# pcb_1.net
KiCad netlist of a schematic drawn in EAGLE
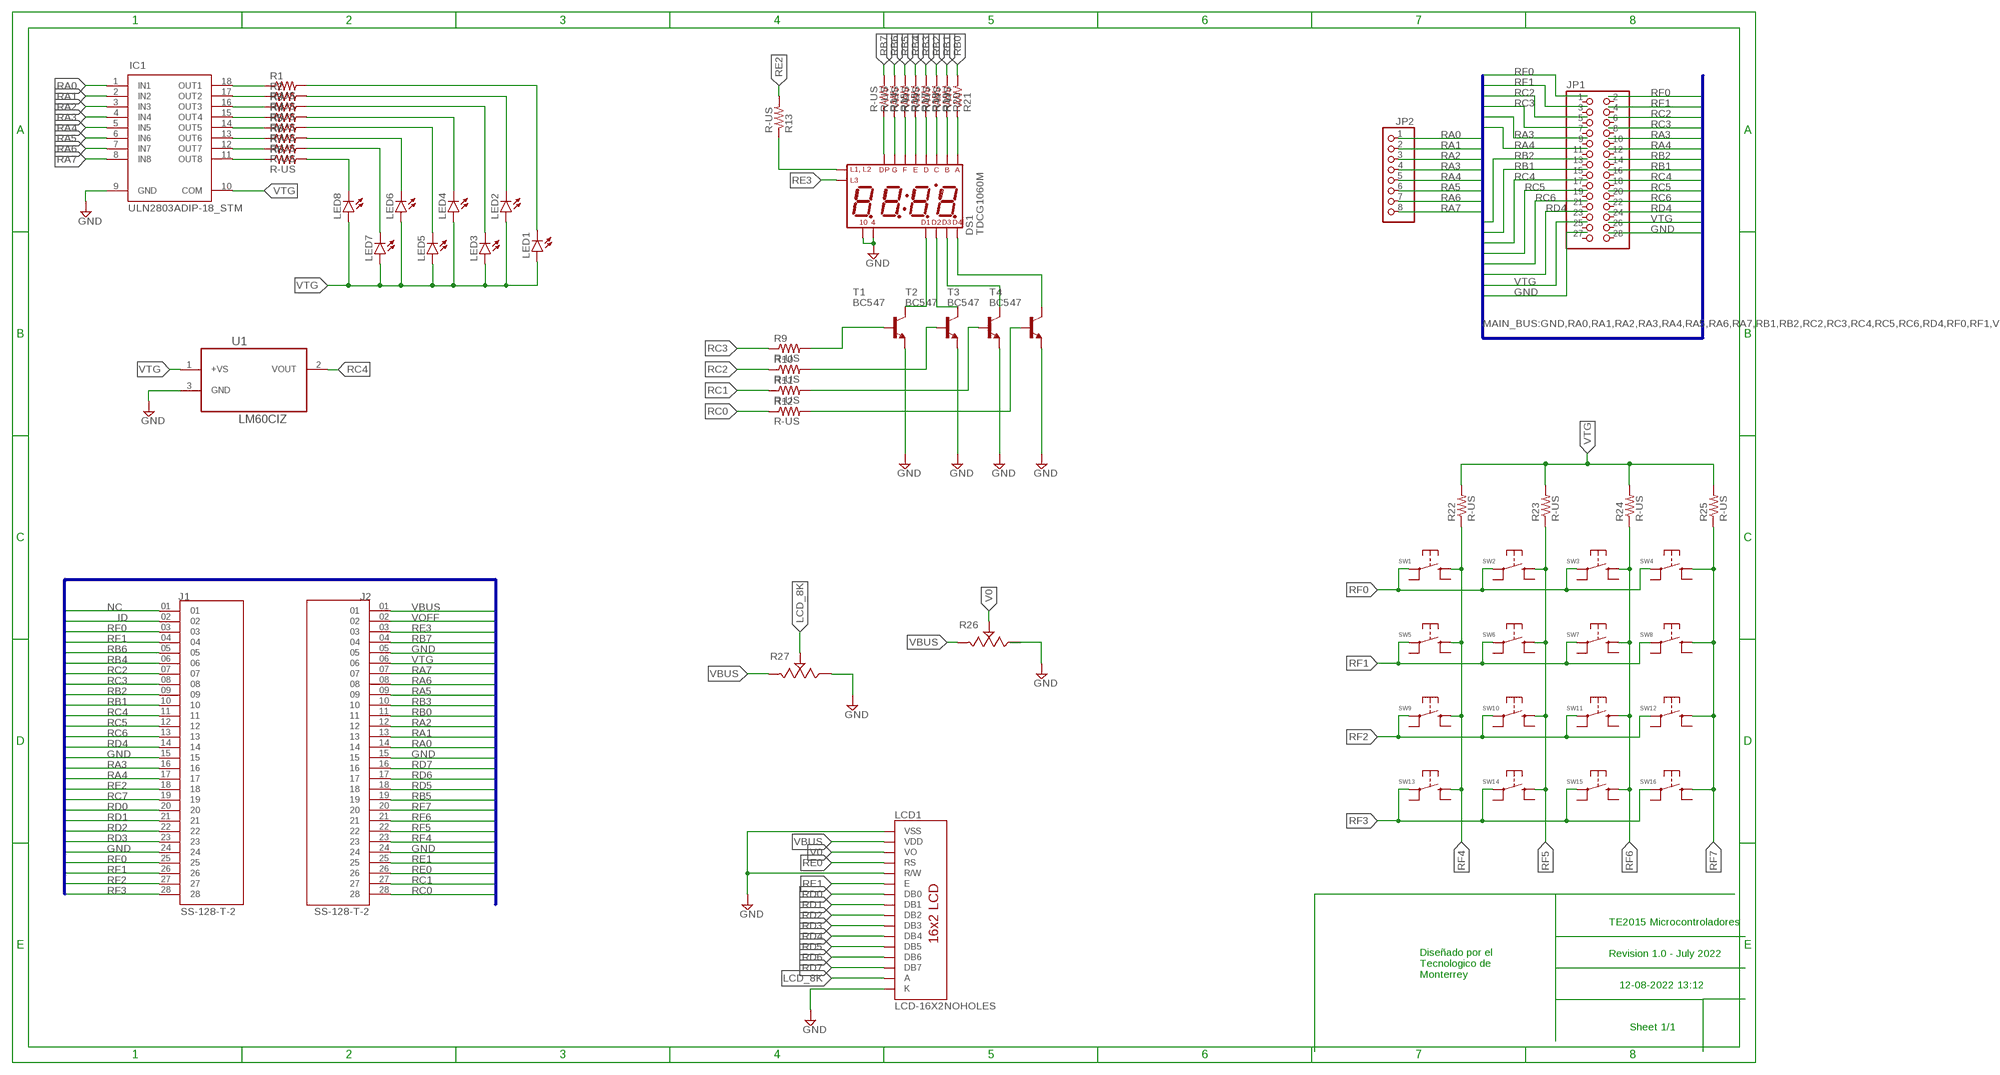
[diagram p0: schematic, sheet 1]

(export (version "E")
  (design (tool "Eeschema 10.0.6"))
  (components
    (comp (ref "DS1")
      (value "TDCG1060M")
      (footprint "eagle-import:DISPLAY_TDCG1060M")
      (fields (field (name "DIGI-KEY_PART_NUMBER") "TDCG1060M-ND") (field (name "MF") "Vishay"))
      (libsource (lib "eagle-import") (part "TDCG1060M"))
    )
    (comp (ref "IC1")
      (value "ULN2803ADIP-18_STM")
      (footprint "eagle-import:DIP-18_STM")
      (fields
        (field (name "MANUFACTURER_PART_NUMBER") "ULN2803A")
        (field (name "COPYRIGHT") "Copyright (C) 2022 Ultra Librarian. All rights reserved.")
      )
      (libsource (lib "eagle-import") (part "ULN2803ADIP-18_STM"))
    )
    (comp (ref "J1")
      (value "SS-128-T-2")
      (footprint "eagle-import:SAMTEC_SS-128-T-2")
      (fields (field (name "DIGI-KEY_PART_NUMBER") "SAM1117-28-ND") (field (name "MF") "Samtec"))
      (libsource (lib "eagle-import") (part "SS-128-T-2"))
    )
    (comp (ref "J2")
      (value "SS-128-T-2")
      (footprint "eagle-import:SAMTEC_SS-128-T-2")
      (fields (field (name "DIGI-KEY_PART_NUMBER") "SAM1117-28-ND") (field (name "MF") "Samtec"))
      (libsource (lib "eagle-import") (part "SS-128-T-2"))
    )
    (comp (ref "JP1")
      (value "PINHD-2X14-CB")
      (footprint "eagle-import:2X14-BIG")
      (libsource (lib "eagle-import") (part "PINHD-2X14-CB"))
    )
    (comp (ref "JP2")
      (value "PINHD-1X8BIG")
      (footprint "eagle-import:1X08-BIG")
      (libsource (lib "eagle-import") (part "PINHD-1X8BIG"))
    )
    (comp (ref "LCD1")
      (value "LCD-16X2NOHOLES")
      (footprint "eagle-import:LCD-16X2_NOHOLESNOSILK")
      (libsource (lib "eagle-import") (part "LCD-16X2NOHOLES"))
    )
    (comp (ref "LED1")
      (value "LED3MM")
      (footprint "eagle-import:LED3MM")
      (libsource (lib "eagle-import") (part "LED3MM"))
    )
    (comp (ref "LED2")
      (value "LED3MM")
      (footprint "eagle-import:LED3MM")
      (libsource (lib "eagle-import") (part "LED3MM"))
    )
    (comp (ref "LED3")
      (value "LED3MM")
      (footprint "eagle-import:LED3MM")
      (libsource (lib "eagle-import") (part "LED3MM"))
    )
    (comp (ref "LED4")
      (value "LED3MM")
      (footprint "eagle-import:LED3MM")
      (libsource (lib "eagle-import") (part "LED3MM"))
    )
    (comp (ref "LED5")
      (value "LED3MM")
      (footprint "eagle-import:LED3MM")
      (libsource (lib "eagle-import") (part "LED3MM"))
    )
    (comp (ref "LED6")
      (value "LED3MM")
      (footprint "eagle-import:LED3MM")
      (libsource (lib "eagle-import") (part "LED3MM"))
    )
    (comp (ref "LED7")
      (value "LED3MM")
      (footprint "eagle-import:LED3MM")
      (libsource (lib "eagle-import") (part "LED3MM"))
    )
    (comp (ref "LED8")
      (value "LED3MM")
      (footprint "eagle-import:LED3MM")
      (libsource (lib "eagle-import") (part "LED3MM"))
    )
    (comp (ref "R1")
      (value "R-US")
      (footprint "eagle-import:0207_10")
      (libsource (lib "eagle-import") (part "R-US"))
    )
    (comp (ref "R2")
      (value "R-US")
      (footprint "eagle-import:0207_10")
      (libsource (lib "eagle-import") (part "R-US"))
    )
    (comp (ref "R3")
      (value "R-US")
      (footprint "eagle-import:0207_10")
      (libsource (lib "eagle-import") (part "R-US"))
    )
    (comp (ref "R4")
      (value "R-US")
      (footprint "eagle-import:0207_10")
      (libsource (lib "eagle-import") (part "R-US"))
    )
    (comp (ref "R5")
      (value "R-US")
      (footprint "eagle-import:0207_10")
      (libsource (lib "eagle-import") (part "R-US"))
    )
    (comp (ref "R6")
      (value "R-US")
      (footprint "eagle-import:0207_10")
      (libsource (lib "eagle-import") (part "R-US"))
    )
    (comp (ref "R7")
      (value "R-US")
      (footprint "eagle-import:0207_10")
      (libsource (lib "eagle-import") (part "R-US"))
    )
    (comp (ref "R8")
      (value "R-US")
      (footprint "eagle-import:0207_10")
      (libsource (lib "eagle-import") (part "R-US"))
    )
    (comp (ref "R9")
      (value "R-US")
      (footprint "eagle-import:0207_10")
      (libsource (lib "eagle-import") (part "R-US"))
    )
    (comp (ref "R10")
      (value "R-US")
      (footprint "eagle-import:0207_10")
      (libsource (lib "eagle-import") (part "R-US"))
    )
    (comp (ref "R11")
      (value "R-US")
      (footprint "eagle-import:0207_10")
      (libsource (lib "eagle-import") (part "R-US"))
    )
    (comp (ref "R12")
      (value "R-US")
      (footprint "eagle-import:0207_10")
      (libsource (lib "eagle-import") (part "R-US"))
    )
    (comp (ref "R13")
      (value "R-US")
      (footprint "eagle-import:0207_10")
      (libsource (lib "eagle-import") (part "R-US"))
    )
    (comp (ref "R14")
      (value "R-US")
      (footprint "eagle-import:0207_10")
      (libsource (lib "eagle-import") (part "R-US"))
    )
    (comp (ref "R15")
      (value "R-US")
      (footprint "eagle-import:0207_10")
      (libsource (lib "eagle-import") (part "R-US"))
    )
    (comp (ref "R16")
      (value "R-US")
      (footprint "eagle-import:0207_10")
      (libsource (lib "eagle-import") (part "R-US"))
    )
    (comp (ref "R17")
      (value "R-US")
      (footprint "eagle-import:0207_10")
      (libsource (lib "eagle-import") (part "R-US"))
    )
    (comp (ref "R18")
      (value "R-US")
      (footprint "eagle-import:0207_10")
      (libsource (lib "eagle-import") (part "R-US"))
    )
    (comp (ref "R19")
      (value "R-US")
      (footprint "eagle-import:0207_10")
      (libsource (lib "eagle-import") (part "R-US"))
    )
    (comp (ref "R20")
      (value "R-US")
      (footprint "eagle-import:0207_10")
      (libsource (lib "eagle-import") (part "R-US"))
    )
    (comp (ref "R21")
      (value "R-US")
      (footprint "eagle-import:0207_10")
      (libsource (lib "eagle-import") (part "R-US"))
    )
    (comp (ref "R22")
      (value "R-US")
      (footprint "eagle-import:0207_10")
      (libsource (lib "eagle-import") (part "R-US"))
    )
    (comp (ref "R23")
      (value "R-US")
      (footprint "eagle-import:0207_10")
      (libsource (lib "eagle-import") (part "R-US"))
    )
    (comp (ref "R24")
      (value "R-US")
      (footprint "eagle-import:0207_10")
      (libsource (lib "eagle-import") (part "R-US"))
    )
    (comp (ref "R25")
      (value "R-US")
      (footprint "eagle-import:0207_10")
      (libsource (lib "eagle-import") (part "R-US"))
    )
    (comp (ref "R26")
      (value "3362P-1-103LF")
      (footprint "eagle-import:3362P-1-103LF")
      (fields (field (name "MANUFACTURER") "Bourns Inc.") (field (name "CREATED_PN") "PCBLayout.com"))
      (libsource (lib "eagle-import") (part "3362P-1-103LF"))
    )
    (comp (ref "R27")
      (value "3362P-1-103LF")
      (footprint "eagle-import:3362P-1-103LF")
      (fields (field (name "MANUFACTURER") "Bourns Inc.") (field (name "CREATED_PN") "PCBLayout.com"))
      (libsource (lib "eagle-import") (part "3362P-1-103LF"))
    )
    (comp (ref "SW1")
      (value "1825910-2")
      (footprint "eagle-import:TE_1825910-2")
      (fields (field (name "MF") "TE Connectivity"))
      (libsource (lib "eagle-import") (part "1825910-2"))
    )
    (comp (ref "SW2")
      (value "1825910-2")
      (footprint "eagle-import:TE_1825910-2")
      (fields (field (name "MF") "TE Connectivity"))
      (libsource (lib "eagle-import") (part "1825910-2"))
    )
    (comp (ref "SW3")
      (value "1825910-2")
      (footprint "eagle-import:TE_1825910-2")
      (fields (field (name "MF") "TE Connectivity"))
      (libsource (lib "eagle-import") (part "1825910-2"))
    )
    (comp (ref "SW4")
      (value "1825910-2")
      (footprint "eagle-import:TE_1825910-2")
      (fields (field (name "MF") "TE Connectivity"))
      (libsource (lib "eagle-import") (part "1825910-2"))
    )
    (comp (ref "SW5")
      (value "1825910-2")
      (footprint "eagle-import:TE_1825910-2")
      (fields (field (name "MF") "TE Connectivity"))
      (libsource (lib "eagle-import") (part "1825910-2"))
    )
    (comp (ref "SW6")
      (value "1825910-2")
      (footprint "eagle-import:TE_1825910-2")
      (fields (field (name "MF") "TE Connectivity"))
      (libsource (lib "eagle-import") (part "1825910-2"))
    )
    (comp (ref "SW7")
      (value "1825910-2")
      (footprint "eagle-import:TE_1825910-2")
      (fields (field (name "MF") "TE Connectivity"))
      (libsource (lib "eagle-import") (part "1825910-2"))
    )
    (comp (ref "SW8")
      (value "1825910-2")
      (footprint "eagle-import:TE_1825910-2")
      (fields (field (name "MF") "TE Connectivity"))
      (libsource (lib "eagle-import") (part "1825910-2"))
    )
    (comp (ref "SW9")
      (value "1825910-2")
      (footprint "eagle-import:TE_1825910-2")
      (fields (field (name "MF") "TE Connectivity"))
      (libsource (lib "eagle-import") (part "1825910-2"))
    )
    (comp (ref "SW10")
      (value "1825910-2")
      (footprint "eagle-import:TE_1825910-2")
      (fields (field (name "MF") "TE Connectivity"))
      (libsource (lib "eagle-import") (part "1825910-2"))
    )
    (comp (ref "SW11")
      (value "1825910-2")
      (footprint "eagle-import:TE_1825910-2")
      (fields (field (name "MF") "TE Connectivity"))
      (libsource (lib "eagle-import") (part "1825910-2"))
    )
    (comp (ref "SW12")
      (value "1825910-2")
      (footprint "eagle-import:TE_1825910-2")
      (fields (field (name "MF") "TE Connectivity"))
      (libsource (lib "eagle-import") (part "1825910-2"))
    )
    (comp (ref "SW13")
      (value "1825910-2")
      (footprint "eagle-import:TE_1825910-2")
      (fields (field (name "MF") "TE Connectivity"))
      (libsource (lib "eagle-import") (part "1825910-2"))
    )
    (comp (ref "SW14")
      (value "1825910-2")
      (footprint "eagle-import:TE_1825910-2")
      (fields (field (name "MF") "TE Connectivity"))
      (libsource (lib "eagle-import") (part "1825910-2"))
    )
    (comp (ref "SW15")
      (value "1825910-2")
      (footprint "eagle-import:TE_1825910-2")
      (fields (field (name "MF") "TE Connectivity"))
      (libsource (lib "eagle-import") (part "1825910-2"))
    )
    (comp (ref "SW16")
      (value "1825910-2")
      (footprint "eagle-import:TE_1825910-2")
      (fields (field (name "MF") "TE Connectivity"))
      (libsource (lib "eagle-import") (part "1825910-2"))
    )
    (comp (ref "T1")
      (value "BC547")
      (footprint "eagle-import:TO92")
      (libsource (lib "eagle-import") (part "BC547"))
    )
    (comp (ref "T2")
      (value "BC547")
      (footprint "eagle-import:TO92")
      (libsource (lib "eagle-import") (part "BC547"))
    )
    (comp (ref "T3")
      (value "BC547")
      (footprint "eagle-import:TO92")
      (libsource (lib "eagle-import") (part "BC547"))
    )
    (comp (ref "T4")
      (value "BC547")
      (footprint "eagle-import:TO92")
      (libsource (lib "eagle-import") (part "BC547"))
    )
    (comp (ref "U1")
      (value "LM60CIZ")
      (footprint "eagle-import:TO92_")
      (libsource (lib "eagle-import") (part "LM60CIZ"))
    )
  )
  (nets
    (net (code "2") (name "/ID") (class "Default")
      (node (ref "J1") (pin "02") (pinfunction "02_02") (pintype "passive"))
    )
    (net (code "3") (name "/NC") (class "Default")
      (node (ref "J1") (pin "01") (pinfunction "01_01") (pintype "passive"))
    )
    (net (code "4") (name "/RC5") (class "Default")
      (node (ref "J1") (pin "12") (pinfunction "12_12") (pintype "passive"))
    )
    (net (code "5") (name "/RC6") (class "Default")
      (node (ref "J1") (pin "13") (pinfunction "13_13") (pintype "passive"))
    )
    (net (code "6") (name "/RC7") (class "Default")
      (node (ref "J1") (pin "19") (pinfunction "19_19") (pintype "passive"))
    )
    (net (code "7") (name "/VOFF") (class "Default")
      (node (ref "J2") (pin "02") (pinfunction "02_02") (pintype "passive"))
    )
    (net (code "9") (name "GND") (class "Default")
      (node (ref "DS1") (pin "10") (pinfunction "10_10") (pintype "passive"))
      (node (ref "DS1") (pin "4") (pinfunction "4_4") (pintype "passive"))
      (node (ref "IC1") (pin "9") (pinfunction "GND_9") (pintype "power_in"))
      (node (ref "J1") (pin "15") (pinfunction "15_15") (pintype "passive"))
      (node (ref "J1") (pin "24") (pinfunction "24_24") (pintype "passive"))
      (node (ref "J2") (pin "05") (pinfunction "05_05") (pintype "passive"))
      (node (ref "J2") (pin "15") (pinfunction "15_15") (pintype "passive"))
      (node (ref "J2") (pin "24") (pinfunction "24_24") (pintype "passive"))
      (node (ref "LCD1") (pin "1") (pinfunction "VSS_1") (pintype "power_in"))
      (node (ref "LCD1") (pin "16") (pinfunction "K_16") (pintype "power_in"))
      (node (ref "LCD1") (pin "5") (pinfunction "R/W_5") (pintype "input"))
      (node (ref "R26") (pin "3") (pinfunction "3_3") (pintype "passive"))
      (node (ref "R27") (pin "3") (pinfunction "3_3") (pintype "passive"))
      (node (ref "T1") (pin "1") (pinfunction "E_1") (pintype "passive"))
      (node (ref "T2") (pin "1") (pinfunction "E_1") (pintype "passive"))
      (node (ref "T3") (pin "1") (pinfunction "E_1") (pintype "passive"))
      (node (ref "T4") (pin "1") (pinfunction "E_1") (pintype "passive"))
      (node (ref "U1") (pin "3") (pinfunction "GND_3") (pintype "passive"))
    )
    (net (code "10") (name "LCD_8K") (class "Default")
      (node (ref "LCD1") (pin "15") (pinfunction "A_15") (pintype "power_in"))
      (node (ref "R27") (pin "2") (pinfunction "2_2") (pintype "passive"))
    )
    (net (code "11") (name "Net-(DS1-A)") (class "Default")
      (node (ref "DS1") (pin "14") (pinfunction "A_14") (pintype "passive"))
      (node (ref "R21") (pin "1") (pinfunction "1_1") (pintype "passive"))
    )
    (net (code "12") (name "Net-(DS1-B)") (class "Default")
      (node (ref "DS1") (pin "16") (pinfunction "B_16") (pintype "passive"))
      (node (ref "R20") (pin "1") (pinfunction "1_1") (pintype "passive"))
    )
    (net (code "13") (name "Net-(DS1-C)") (class "Default")
      (node (ref "DS1") (pin "13") (pinfunction "C_13") (pintype "passive"))
      (node (ref "R19") (pin "1") (pinfunction "1_1") (pintype "passive"))
    )
    (net (code "14") (name "Net-(DS1-D)") (class "Default")
      (node (ref "DS1") (pin "3") (pinfunction "D_3") (pintype "passive"))
      (node (ref "R18") (pin "1") (pinfunction "1_1") (pintype "passive"))
    )
    (net (code "15") (name "Net-(DS1-DIG1)") (class "Default")
      (node (ref "DS1") (pin "1") (pinfunction "DIG1_1") (pintype "passive"))
      (node (ref "T1") (pin "3") (pinfunction "C_3") (pintype "passive"))
    )
    (net (code "16") (name "Net-(DS1-DIG2)") (class "Default")
      (node (ref "DS1") (pin "2") (pinfunction "DIG2_2") (pintype "passive"))
      (node (ref "T2") (pin "3") (pinfunction "C_3") (pintype "passive"))
    )
    (net (code "17") (name "Net-(DS1-DIG3)") (class "Default")
      (node (ref "DS1") (pin "6") (pinfunction "DIG3_6") (pintype "passive"))
      (node (ref "T3") (pin "3") (pinfunction "C_3") (pintype "passive"))
    )
    (net (code "18") (name "Net-(DS1-DIG4)") (class "Default")
      (node (ref "DS1") (pin "8") (pinfunction "DIG4_8") (pintype "passive"))
      (node (ref "T4") (pin "3") (pinfunction "C_3") (pintype "passive"))
    )
    (net (code "19") (name "Net-(DS1-DP)") (class "Default")
      (node (ref "DS1") (pin "7") (pinfunction "DP_7") (pintype "passive"))
      (node (ref "R14") (pin "1") (pinfunction "1_1") (pintype "passive"))
    )
    (net (code "20") (name "Net-(DS1-E)") (class "Default")
      (node (ref "DS1") (pin "5") (pinfunction "E_5") (pintype "passive"))
      (node (ref "R17") (pin "1") (pinfunction "1_1") (pintype "passive"))
    )
    (net (code "21") (name "Net-(DS1-F)") (class "Default")
      (node (ref "DS1") (pin "11") (pinfunction "F_11") (pintype "passive"))
      (node (ref "R16") (pin "1") (pinfunction "1_1") (pintype "passive"))
    )
    (net (code "22") (name "Net-(DS1-G)") (class "Default")
      (node (ref "DS1") (pin "15") (pinfunction "G_15") (pintype "passive"))
      (node (ref "R15") (pin "1") (pinfunction "1_1") (pintype "passive"))
    )
    (net (code "23") (name "Net-(DS1-L1_L2)") (class "Default")
      (node (ref "DS1") (pin "12") (pinfunction "L1_L2_12") (pintype "passive"))
      (node (ref "R13") (pin "1") (pinfunction "1_1") (pintype "passive"))
    )
    (net (code "24") (name "Net-(IC1-OUT1)") (class "Default")
      (node (ref "IC1") (pin "18") (pinfunction "OUT1_18") (pintype "passive"))
      (node (ref "R1") (pin "1") (pinfunction "1_1") (pintype "passive"))
    )
    (net (code "25") (name "Net-(IC1-OUT2)") (class "Default")
      (node (ref "IC1") (pin "17") (pinfunction "OUT2_17") (pintype "passive"))
      (node (ref "R2") (pin "1") (pinfunction "1_1") (pintype "passive"))
    )
    (net (code "26") (name "Net-(IC1-OUT3)") (class "Default")
      (node (ref "IC1") (pin "16") (pinfunction "OUT3_16") (pintype "passive"))
      (node (ref "R3") (pin "1") (pinfunction "1_1") (pintype "passive"))
    )
    (net (code "27") (name "Net-(IC1-OUT4)") (class "Default")
      (node (ref "IC1") (pin "15") (pinfunction "OUT4_15") (pintype "passive"))
      (node (ref "R4") (pin "1") (pinfunction "1_1") (pintype "passive"))
    )
    (net (code "28") (name "Net-(IC1-OUT5)") (class "Default")
      (node (ref "IC1") (pin "14") (pinfunction "OUT5_14") (pintype "passive"))
      (node (ref "R5") (pin "1") (pinfunction "1_1") (pintype "passive"))
    )
    (net (code "29") (name "Net-(IC1-OUT6)") (class "Default")
      (node (ref "IC1") (pin "13") (pinfunction "OUT6_13") (pintype "passive"))
      (node (ref "R6") (pin "1") (pinfunction "1_1") (pintype "passive"))
    )
    (net (code "30") (name "Net-(IC1-OUT7)") (class "Default")
      (node (ref "IC1") (pin "12") (pinfunction "OUT7_12") (pintype "passive"))
      (node (ref "R7") (pin "1") (pinfunction "1_1") (pintype "passive"))
    )
    (net (code "31") (name "Net-(IC1-OUT8)") (class "Default")
      (node (ref "IC1") (pin "11") (pinfunction "OUT8_11") (pintype "passive"))
      (node (ref "R8") (pin "1") (pinfunction "1_1") (pintype "passive"))
    )
    (net (code "32") (name "Net-(LED1-C)") (class "Default")
      (node (ref "LED1") (pin "K") (pinfunction "C_K") (pintype "passive"))
      (node (ref "R1") (pin "2") (pinfunction "2_2") (pintype "passive"))
    )
    (net (code "33") (name "Net-(LED2-C)") (class "Default")
      (node (ref "LED2") (pin "K") (pinfunction "C_K") (pintype "passive"))
      (node (ref "R2") (pin "2") (pinfunction "2_2") (pintype "passive"))
    )
    (net (code "34") (name "Net-(LED3-C)") (class "Default")
      (node (ref "LED3") (pin "K") (pinfunction "C_K") (pintype "passive"))
      (node (ref "R3") (pin "2") (pinfunction "2_2") (pintype "passive"))
    )
    (net (code "35") (name "Net-(LED4-C)") (class "Default")
      (node (ref "LED4") (pin "K") (pinfunction "C_K") (pintype "passive"))
      (node (ref "R4") (pin "2") (pinfunction "2_2") (pintype "passive"))
    )
    (net (code "36") (name "Net-(LED5-C)") (class "Default")
      (node (ref "LED5") (pin "K") (pinfunction "C_K") (pintype "passive"))
      (node (ref "R5") (pin "2") (pinfunction "2_2") (pintype "passive"))
    )
    (net (code "37") (name "Net-(LED6-C)") (class "Default")
      (node (ref "LED6") (pin "K") (pinfunction "C_K") (pintype "passive"))
      (node (ref "R6") (pin "2") (pinfunction "2_2") (pintype "passive"))
    )
    (net (code "38") (name "Net-(LED7-C)") (class "Default")
      (node (ref "LED7") (pin "K") (pinfunction "C_K") (pintype "passive"))
      (node (ref "R7") (pin "2") (pinfunction "2_2") (pintype "passive"))
    )
    (net (code "39") (name "Net-(LED8-C)") (class "Default")
      (node (ref "LED8") (pin "K") (pinfunction "C_K") (pintype "passive"))
      (node (ref "R8") (pin "2") (pinfunction "2_2") (pintype "passive"))
    )
    (net (code "40") (name "Net-(T1-B)") (class "Default")
      (node (ref "R9") (pin "2") (pinfunction "2_2") (pintype "passive"))
      (node (ref "T1") (pin "2") (pinfunction "B_2") (pintype "passive"))
    )
    (net (code "41") (name "Net-(T2-B)") (class "Default")
      (node (ref "R10") (pin "2") (pinfunction "2_2") (pintype "passive"))
      (node (ref "T2") (pin "2") (pinfunction "B_2") (pintype "passive"))
    )
    (net (code "42") (name "Net-(T3-B)") (class "Default")
      (node (ref "R11") (pin "2") (pinfunction "2_2") (pintype "passive"))
      (node (ref "T3") (pin "2") (pinfunction "B_2") (pintype "passive"))
    )
    (net (code "43") (name "Net-(T4-B)") (class "Default")
      (node (ref "R12") (pin "2") (pinfunction "2_2") (pintype "passive"))
      (node (ref "T4") (pin "2") (pinfunction "B_2") (pintype "passive"))
    )
    (net (code "44") (name "RA0") (class "Default")
      (node (ref "IC1") (pin "1") (pinfunction "IN1_1") (pintype "input"))
      (node (ref "J2") (pin "14") (pinfunction "14_14") (pintype "passive"))
      (node (ref "JP2") (pin "1") (pinfunction "1_1") (pintype "passive"))
    )
    (net (code "45") (name "RA1") (class "Default")
      (node (ref "IC1") (pin "2") (pinfunction "IN2_2") (pintype "input"))
      (node (ref "J2") (pin "13") (pinfunction "13_13") (pintype "passive"))
      (node (ref "JP2") (pin "2") (pinfunction "2_2") (pintype "passive"))
    )
    (net (code "46") (name "RA2") (class "Default")
      (node (ref "IC1") (pin "3") (pinfunction "IN3_3") (pintype "input"))
      (node (ref "J2") (pin "12") (pinfunction "12_12") (pintype "passive"))
      (node (ref "JP2") (pin "3") (pinfunction "3_3") (pintype "passive"))
    )
    (net (code "47") (name "RA3") (class "Default")
      (node (ref "IC1") (pin "4") (pinfunction "IN4_4") (pintype "input"))
      (node (ref "J1") (pin "16") (pinfunction "16_16") (pintype "passive"))
      (node (ref "JP2") (pin "4") (pinfunction "4_4") (pintype "passive"))
    )
    (net (code "48") (name "RA4") (class "Default")
      (node (ref "IC1") (pin "5") (pinfunction "IN5_5") (pintype "input"))
      (node (ref "J1") (pin "17") (pinfunction "17_17") (pintype "passive"))
      (node (ref "JP2") (pin "5") (pinfunction "5_5") (pintype "passive"))
    )
    (net (code "49") (name "RA5") (class "Default")
      (node (ref "IC1") (pin "6") (pinfunction "IN6_6") (pintype "input"))
      (node (ref "J2") (pin "09") (pinfunction "09_09") (pintype "passive"))
      (node (ref "JP2") (pin "6") (pinfunction "6_6") (pintype "passive"))
    )
    (net (code "50") (name "RA6") (class "Default")
      (node (ref "IC1") (pin "7") (pinfunction "IN7_7") (pintype "input"))
      (node (ref "J2") (pin "08") (pinfunction "08_08") (pintype "passive"))
      (node (ref "JP2") (pin "7") (pinfunction "7_7") (pintype "passive"))
    )
    (net (code "51") (name "RA7") (class "Default")
      (node (ref "IC1") (pin "8") (pinfunction "IN8_8") (pintype "input"))
      (node (ref "J2") (pin "07") (pinfunction "07_07") (pintype "passive"))
      (node (ref "JP2") (pin "8") (pinfunction "8_8") (pintype "passive"))
    )
    (net (code "52") (name "RB0") (class "Default")
      (node (ref "J2") (pin "11") (pinfunction "11_11") (pintype "passive"))
      (node (ref "R21") (pin "2") (pinfunction "2_2") (pintype "passive"))
    )
    (net (code "53") (name "RB1") (class "Default")
      (node (ref "J1") (pin "10") (pinfunction "10_10") (pintype "passive"))
      (node (ref "R20") (pin "2") (pinfunction "2_2") (pintype "passive"))
    )
    (net (code "54") (name "RB2") (class "Default")
      (node (ref "J1") (pin "09") (pinfunction "09_09") (pintype "passive"))
      (node (ref "R19") (pin "2") (pinfunction "2_2") (pintype "passive"))
    )
    (net (code "55") (name "RB3") (class "Default")
      (node (ref "J2") (pin "10") (pinfunction "10_10") (pintype "passive"))
      (node (ref "R18") (pin "2") (pinfunction "2_2") (pintype "passive"))
    )
    (net (code "56") (name "RB4") (class "Default")
      (node (ref "J1") (pin "06") (pinfunction "06_06") (pintype "passive"))
      (node (ref "R17") (pin "2") (pinfunction "2_2") (pintype "passive"))
    )
    (net (code "57") (name "RB5") (class "Default")
      (node (ref "J2") (pin "19") (pinfunction "19_19") (pintype "passive"))
      (node (ref "R16") (pin "2") (pinfunction "2_2") (pintype "passive"))
    )
    (net (code "58") (name "RB6") (class "Default")
      (node (ref "J1") (pin "05") (pinfunction "05_05") (pintype "passive"))
      (node (ref "R15") (pin "2") (pinfunction "2_2") (pintype "passive"))
    )
    (net (code "59") (name "RB7") (class "Default")
      (node (ref "J2") (pin "04") (pinfunction "04_04") (pintype "passive"))
      (node (ref "R14") (pin "2") (pinfunction "2_2") (pintype "passive"))
    )
    (net (code "60") (name "RC0") (class "Default")
      (node (ref "J2") (pin "28") (pinfunction "28_28") (pintype "passive"))
      (node (ref "R12") (pin "1") (pinfunction "1_1") (pintype "passive"))
    )
    (net (code "61") (name "RC1") (class "Default")
      (node (ref "J2") (pin "27") (pinfunction "27_27") (pintype "passive"))
      (node (ref "R11") (pin "1") (pinfunction "1_1") (pintype "passive"))
    )
    (net (code "62") (name "RC2") (class "Default")
      (node (ref "J1") (pin "07") (pinfunction "07_07") (pintype "passive"))
      (node (ref "R10") (pin "1") (pinfunction "1_1") (pintype "passive"))
    )
    (net (code "63") (name "RC3") (class "Default")
      (node (ref "J1") (pin "08") (pinfunction "08_08") (pintype "passive"))
      (node (ref "R9") (pin "1") (pinfunction "1_1") (pintype "passive"))
    )
    (net (code "64") (name "RC4") (class "Default")
      (node (ref "J1") (pin "11") (pinfunction "11_11") (pintype "passive"))
      (node (ref "U1") (pin "2") (pinfunction "VOUT_2") (pintype "output"))
    )
    (net (code "65") (name "RD0") (class "Default")
      (node (ref "J1") (pin "20") (pinfunction "20_20") (pintype "passive"))
      (node (ref "LCD1") (pin "7") (pinfunction "DB0_7") (pintype "bidirectional"))
    )
    (net (code "66") (name "RD1") (class "Default")
      (node (ref "J1") (pin "21") (pinfunction "21_21") (pintype "passive"))
      (node (ref "LCD1") (pin "8") (pinfunction "DB1_8") (pintype "bidirectional"))
    )
    (net (code "67") (name "RD2") (class "Default")
      (node (ref "J1") (pin "22") (pinfunction "22_22") (pintype "passive"))
      (node (ref "LCD1") (pin "9") (pinfunction "DB2_9") (pintype "bidirectional"))
    )
    (net (code "68") (name "RD3") (class "Default")
      (node (ref "J1") (pin "23") (pinfunction "23_23") (pintype "passive"))
      (node (ref "LCD1") (pin "10") (pinfunction "DB3_10") (pintype "bidirectional"))
    )
    (net (code "69") (name "RD4") (class "Default")
      (node (ref "J1") (pin "14") (pinfunction "14_14") (pintype "passive"))
      (node (ref "LCD1") (pin "11") (pinfunction "DB4_11") (pintype "bidirectional"))
    )
    (net (code "70") (name "RD5") (class "Default")
      (node (ref "J2") (pin "18") (pinfunction "18_18") (pintype "passive"))
      (node (ref "LCD1") (pin "12") (pinfunction "DB5_12") (pintype "bidirectional"))
    )
    (net (code "71") (name "RD6") (class "Default")
      (node (ref "J2") (pin "17") (pinfunction "17_17") (pintype "passive"))
      (node (ref "LCD1") (pin "13") (pinfunction "DB6_13") (pintype "bidirectional"))
    )
    (net (code "72") (name "RD7") (class "Default")
      (node (ref "J2") (pin "16") (pinfunction "16_16") (pintype "passive"))
      (node (ref "LCD1") (pin "14") (pinfunction "DB7_14") (pintype "bidirectional"))
    )
    (net (code "73") (name "RE0") (class "Default")
      (node (ref "J2") (pin "26") (pinfunction "26_26") (pintype "passive"))
      (node (ref "LCD1") (pin "4") (pinfunction "RS_4") (pintype "input"))
    )
    (net (code "74") (name "RE1") (class "Default")
      (node (ref "J2") (pin "25") (pinfunction "25_25") (pintype "passive"))
      (node (ref "LCD1") (pin "6") (pinfunction "E_6") (pintype "input"))
    )
    (net (code "75") (name "RE2") (class "Default")
      (node (ref "J1") (pin "18") (pinfunction "18_18") (pintype "passive"))
      (node (ref "R13") (pin "2") (pinfunction "2_2") (pintype "passive"))
    )
    (net (code "76") (name "RE3") (class "Default")
      (node (ref "DS1") (pin "9") (pinfunction "L3_9") (pintype "passive"))
      (node (ref "J2") (pin "03") (pinfunction "03_03") (pintype "passive"))
    )
    (net (code "77") (name "RF0") (class "Default")
      (node (ref "J1") (pin "03") (pinfunction "03_03") (pintype "passive"))
      (node (ref "J1") (pin "25") (pinfunction "25_25") (pintype "passive"))
      (node (ref "SW1") (pin "1") (pinfunction "P_1") (pintype "passive"))
      (node (ref "SW2") (pin "1") (pinfunction "P_1") (pintype "passive"))
      (node (ref "SW3") (pin "1") (pinfunction "P_1") (pintype "passive"))
      (node (ref "SW4") (pin "1") (pinfunction "P_1") (pintype "passive"))
    )
    (net (code "78") (name "RF1") (class "Default")
      (node (ref "J1") (pin "04") (pinfunction "04_04") (pintype "passive"))
      (node (ref "J1") (pin "26") (pinfunction "26_26") (pintype "passive"))
      (node (ref "SW5") (pin "1") (pinfunction "P_1") (pintype "passive"))
      (node (ref "SW6") (pin "1") (pinfunction "P_1") (pintype "passive"))
      (node (ref "SW7") (pin "1") (pinfunction "P_1") (pintype "passive"))
      (node (ref "SW8") (pin "1") (pinfunction "P_1") (pintype "passive"))
    )
    (net (code "79") (name "RF2") (class "Default")
      (node (ref "J1") (pin "27") (pinfunction "27_27") (pintype "passive"))
      (node (ref "SW10") (pin "1") (pinfunction "P_1") (pintype "passive"))
      (node (ref "SW11") (pin "1") (pinfunction "P_1") (pintype "passive"))
      (node (ref "SW12") (pin "1") (pinfunction "P_1") (pintype "passive"))
      (node (ref "SW9") (pin "1") (pinfunction "P_1") (pintype "passive"))
    )
    (net (code "80") (name "RF3") (class "Default")
      (node (ref "J1") (pin "28") (pinfunction "28_28") (pintype "passive"))
      (node (ref "SW13") (pin "1") (pinfunction "P_1") (pintype "passive"))
      (node (ref "SW14") (pin "1") (pinfunction "P_1") (pintype "passive"))
      (node (ref "SW15") (pin "1") (pinfunction "P_1") (pintype "passive"))
      (node (ref "SW16") (pin "1") (pinfunction "P_1") (pintype "passive"))
    )
    (net (code "81") (name "RF4") (class "Default")
      (node (ref "J2") (pin "23") (pinfunction "23_23") (pintype "passive"))
      (node (ref "R22") (pin "1") (pinfunction "1_1") (pintype "passive"))
      (node (ref "SW1") (pin "2") (pinfunction "S_2") (pintype "passive"))
      (node (ref "SW13") (pin "2") (pinfunction "S_2") (pintype "passive"))
      (node (ref "SW5") (pin "2") (pinfunction "S_2") (pintype "passive"))
      (node (ref "SW9") (pin "2") (pinfunction "S_2") (pintype "passive"))
    )
    (net (code "82") (name "RF5") (class "Default")
      (node (ref "J2") (pin "22") (pinfunction "22_22") (pintype "passive"))
      (node (ref "R23") (pin "1") (pinfunction "1_1") (pintype "passive"))
      (node (ref "SW10") (pin "2") (pinfunction "S_2") (pintype "passive"))
      (node (ref "SW14") (pin "2") (pinfunction "S_2") (pintype "passive"))
      (node (ref "SW2") (pin "2") (pinfunction "S_2") (pintype "passive"))
      (node (ref "SW6") (pin "2") (pinfunction "S_2") (pintype "passive"))
    )
    (net (code "83") (name "RF6") (class "Default")
      (node (ref "J2") (pin "21") (pinfunction "21_21") (pintype "passive"))
      (node (ref "R24") (pin "1") (pinfunction "1_1") (pintype "passive"))
      (node (ref "SW11") (pin "2") (pinfunction "S_2") (pintype "passive"))
      (node (ref "SW15") (pin "2") (pinfunction "S_2") (pintype "passive"))
      (node (ref "SW3") (pin "2") (pinfunction "S_2") (pintype "passive"))
      (node (ref "SW7") (pin "2") (pinfunction "S_2") (pintype "passive"))
    )
    (net (code "84") (name "RF7") (class "Default")
      (node (ref "J2") (pin "20") (pinfunction "20_20") (pintype "passive"))
      (node (ref "R25") (pin "1") (pinfunction "1_1") (pintype "passive"))
      (node (ref "SW12") (pin "2") (pinfunction "S_2") (pintype "passive"))
      (node (ref "SW16") (pin "2") (pinfunction "S_2") (pintype "passive"))
      (node (ref "SW4") (pin "2") (pinfunction "S_2") (pintype "passive"))
      (node (ref "SW8") (pin "2") (pinfunction "S_2") (pintype "passive"))
    )
    (net (code "85") (name "V0") (class "Default")
      (node (ref "LCD1") (pin "3") (pinfunction "VO_3") (pintype "bidirectional"))
      (node (ref "R26") (pin "2") (pinfunction "2_2") (pintype "passive"))
    )
    (net (code "86") (name "VBUS") (class "Default")
      (node (ref "J2") (pin "01") (pinfunction "01_01") (pintype "passive"))
      (node (ref "LCD1") (pin "2") (pinfunction "VDD_2") (pintype "power_in"))
      (node (ref "R26") (pin "1") (pinfunction "1_1") (pintype "passive"))
      (node (ref "R27") (pin "1") (pinfunction "1_1") (pintype "passive"))
    )
    (net (code "87") (name "VTG") (class "Default")
      (node (ref "IC1") (pin "10") (pinfunction "COM_10") (pintype "passive"))
      (node (ref "J2") (pin "06") (pinfunction "06_06") (pintype "passive"))
      (node (ref "LED1") (pin "A") (pinfunction "A_A") (pintype "passive"))
      (node (ref "LED2") (pin "A") (pinfunction "A_A") (pintype "passive"))
      (node (ref "LED3") (pin "A") (pinfunction "A_A") (pintype "passive"))
      (node (ref "LED4") (pin "A") (pinfunction "A_A") (pintype "passive"))
      (node (ref "LED5") (pin "A") (pinfunction "A_A") (pintype "passive"))
      (node (ref "LED6") (pin "A") (pinfunction "A_A") (pintype "passive"))
      (node (ref "LED7") (pin "A") (pinfunction "A_A") (pintype "passive"))
      (node (ref "LED8") (pin "A") (pinfunction "A_A") (pintype "passive"))
      (node (ref "R22") (pin "2") (pinfunction "2_2") (pintype "passive"))
      (node (ref "R23") (pin "2") (pinfunction "2_2") (pintype "passive"))
      (node (ref "R24") (pin "2") (pinfunction "2_2") (pintype "passive"))
      (node (ref "R25") (pin "2") (pinfunction "2_2") (pintype "passive"))
      (node (ref "U1") (pin "1") (pinfunction "+VS_1") (pintype "power_in"))
    )
    (net (code "88") (name "unconnected-(JP1-Pad1)") (class "Default")
      (node (ref "JP1") (pin "1") (pinfunction "1_1") (pintype "passive"))
    )
    (net (code "89") (name "unconnected-(JP1-Pad2)") (class "Default")
      (node (ref "JP1") (pin "2") (pinfunction "2_2") (pintype "passive"))
    )
    (net (code "90") (name "unconnected-(JP1-Pad3)") (class "Default")
      (node (ref "JP1") (pin "3") (pinfunction "3_3") (pintype "passive"))
    )
    (net (code "91") (name "unconnected-(JP1-Pad4)") (class "Default")
      (node (ref "JP1") (pin "4") (pinfunction "4_4") (pintype "passive"))
    )
    (net (code "92") (name "unconnected-(JP1-Pad5)") (class "Default")
      (node (ref "JP1") (pin "5") (pinfunction "5_5") (pintype "passive"))
    )
    (net (code "93") (name "unconnected-(JP1-Pad6)") (class "Default")
      (node (ref "JP1") (pin "6") (pinfunction "6_6") (pintype "passive"))
    )
    (net (code "94") (name "unconnected-(JP1-Pad7)") (class "Default")
      (node (ref "JP1") (pin "7") (pinfunction "7_7") (pintype "passive"))
    )
    (net (code "95") (name "unconnected-(JP1-Pad8)") (class "Default")
      (node (ref "JP1") (pin "8") (pinfunction "8_8") (pintype "passive"))
    )
    (net (code "96") (name "unconnected-(JP1-Pad9)") (class "Default")
      (node (ref "JP1") (pin "9") (pinfunction "9_9") (pintype "passive"))
    )
    (net (code "97") (name "unconnected-(JP1-Pad10)") (class "Default")
      (node (ref "JP1") (pin "10") (pinfunction "10_10") (pintype "passive"))
    )
    (net (code "98") (name "unconnected-(JP1-Pad11)") (class "Default")
      (node (ref "JP1") (pin "11") (pinfunction "11_11") (pintype "passive"))
    )
    (net (code "99") (name "unconnected-(JP1-Pad12)") (class "Default")
      (node (ref "JP1") (pin "12") (pinfunction "12_12") (pintype "passive"))
    )
    (net (code "100") (name "unconnected-(JP1-Pad13)") (class "Default")
      (node (ref "JP1") (pin "13") (pinfunction "13_13") (pintype "passive"))
    )
    (net (code "101") (name "unconnected-(JP1-Pad14)") (class "Default")
      (node (ref "JP1") (pin "14") (pinfunction "14_14") (pintype "passive"))
    )
    (net (code "102") (name "unconnected-(JP1-Pad15)") (class "Default")
      (node (ref "JP1") (pin "15") (pinfunction "15_15") (pintype "passive"))
    )
    (net (code "103") (name "unconnected-(JP1-Pad16)") (class "Default")
      (node (ref "JP1") (pin "16") (pinfunction "16_16") (pintype "passive"))
    )
    (net (code "104") (name "unconnected-(JP1-Pad17)") (class "Default")
      (node (ref "JP1") (pin "17") (pinfunction "17_17") (pintype "passive"))
    )
    (net (code "105") (name "unconnected-(JP1-Pad18)") (class "Default")
      (node (ref "JP1") (pin "18") (pinfunction "18_18") (pintype "passive"))
    )
    (net (code "106") (name "unconnected-(JP1-Pad19)") (class "Default")
      (node (ref "JP1") (pin "19") (pinfunction "19_19") (pintype "passive"))
    )
    (net (code "107") (name "unconnected-(JP1-Pad20)") (class "Default")
      (node (ref "JP1") (pin "20") (pinfunction "20_20") (pintype "passive"))
    )
    (net (code "108") (name "unconnected-(JP1-Pad21)") (class "Default")
      (node (ref "JP1") (pin "21") (pinfunction "21_21") (pintype "passive"))
    )
    (net (code "109") (name "unconnected-(JP1-Pad22)") (class "Default")
      (node (ref "JP1") (pin "22") (pinfunction "22_22") (pintype "passive"))
    )
    (net (code "110") (name "unconnected-(JP1-Pad23)") (class "Default")
      (node (ref "JP1") (pin "23") (pinfunction "23_23") (pintype "passive"))
    )
    (net (code "111") (name "unconnected-(JP1-Pad24)") (class "Default")
      (node (ref "JP1") (pin "24") (pinfunction "24_24") (pintype "passive"))
    )
    (net (code "112") (name "unconnected-(JP1-Pad25)") (class "Default")
      (node (ref "JP1") (pin "25") (pinfunction "25_25") (pintype "passive"))
    )
    (net (code "113") (name "unconnected-(JP1-Pad26)") (class "Default")
      (node (ref "JP1") (pin "26") (pinfunction "26_26") (pintype "passive"))
    )
    (net (code "114") (name "unconnected-(JP1-Pad27)") (class "Default")
      (node (ref "JP1") (pin "27") (pinfunction "27_27") (pintype "passive"))
    )
    (net (code "115") (name "unconnected-(JP1-Pad28)") (class "Default")
      (node (ref "JP1") (pin "28") (pinfunction "28_28") (pintype "passive"))
    )
    (net (code "116") (name "unconnected-(SW1-P1-Pad3)") (class "Default")
      (node (ref "SW1") (pin "3") (pinfunction "P1_3") (pintype "passive"))
    )
    (net (code "117") (name "unconnected-(SW1-S1-Pad4)") (class "Default")
      (node (ref "SW1") (pin "4") (pinfunction "S1_4") (pintype "passive"))
    )
    (net (code "118") (name "unconnected-(SW2-P1-Pad3)") (class "Default")
      (node (ref "SW2") (pin "3") (pinfunction "P1_3") (pintype "passive"))
    )
    (net (code "119") (name "unconnected-(SW2-S1-Pad4)") (class "Default")
      (node (ref "SW2") (pin "4") (pinfunction "S1_4") (pintype "passive"))
    )
    (net (code "120") (name "unconnected-(SW3-P1-Pad3)") (class "Default")
      (node (ref "SW3") (pin "3") (pinfunction "P1_3") (pintype "passive"))
    )
    (net (code "121") (name "unconnected-(SW3-S1-Pad4)") (class "Default")
      (node (ref "SW3") (pin "4") (pinfunction "S1_4") (pintype "passive"))
    )
    (net (code "122") (name "unconnected-(SW4-P1-Pad3)") (class "Default")
      (node (ref "SW4") (pin "3") (pinfunction "P1_3") (pintype "passive"))
    )
    (net (code "123") (name "unconnected-(SW4-S1-Pad4)") (class "Default")
      (node (ref "SW4") (pin "4") (pinfunction "S1_4") (pintype "passive"))
    )
    (net (code "124") (name "unconnected-(SW5-P1-Pad3)") (class "Default")
      (node (ref "SW5") (pin "3") (pinfunction "P1_3") (pintype "passive"))
    )
    (net (code "125") (name "unconnected-(SW5-S1-Pad4)") (class "Default")
      (node (ref "SW5") (pin "4") (pinfunction "S1_4") (pintype "passive"))
    )
    (net (code "126") (name "unconnected-(SW6-P1-Pad3)") (class "Default")
      (node (ref "SW6") (pin "3") (pinfunction "P1_3") (pintype "passive"))
    )
    (net (code "127") (name "unconnected-(SW6-S1-Pad4)") (class "Default")
      (node (ref "SW6") (pin "4") (pinfunction "S1_4") (pintype "passive"))
    )
    (net (code "128") (name "unconnected-(SW7-P1-Pad3)") (class "Default")
      (node (ref "SW7") (pin "3") (pinfunction "P1_3") (pintype "passive"))
    )
    (net (code "129") (name "unconnected-(SW7-S1-Pad4)") (class "Default")
      (node (ref "SW7") (pin "4") (pinfunction "S1_4") (pintype "passive"))
    )
    (net (code "130") (name "unconnected-(SW8-P1-Pad3)") (class "Default")
      (node (ref "SW8") (pin "3") (pinfunction "P1_3") (pintype "passive"))
    )
    (net (code "131") (name "unconnected-(SW8-S1-Pad4)") (class "Default")
      (node (ref "SW8") (pin "4") (pinfunction "S1_4") (pintype "passive"))
    )
    (net (code "132") (name "unconnected-(SW9-P1-Pad3)") (class "Default")
      (node (ref "SW9") (pin "3") (pinfunction "P1_3") (pintype "passive"))
    )
    (net (code "133") (name "unconnected-(SW9-S1-Pad4)") (class "Default")
      (node (ref "SW9") (pin "4") (pinfunction "S1_4") (pintype "passive"))
    )
    (net (code "134") (name "unconnected-(SW10-P1-Pad3)") (class "Default")
      (node (ref "SW10") (pin "3") (pinfunction "P1_3") (pintype "passive"))
    )
    (net (code "135") (name "unconnected-(SW10-S1-Pad4)") (class "Default")
      (node (ref "SW10") (pin "4") (pinfunction "S1_4") (pintype "passive"))
    )
    (net (code "136") (name "unconnected-(SW11-P1-Pad3)") (class "Default")
      (node (ref "SW11") (pin "3") (pinfunction "P1_3") (pintype "passive"))
    )
    (net (code "137") (name "unconnected-(SW11-S1-Pad4)") (class "Default")
      (node (ref "SW11") (pin "4") (pinfunction "S1_4") (pintype "passive"))
    )
    (net (code "138") (name "unconnected-(SW12-P1-Pad3)") (class "Default")
      (node (ref "SW12") (pin "3") (pinfunction "P1_3") (pintype "passive"))
    )
    (net (code "139") (name "unconnected-(SW12-S1-Pad4)") (class "Default")
      (node (ref "SW12") (pin "4") (pinfunction "S1_4") (pintype "passive"))
    )
    (net (code "140") (name "unconnected-(SW13-P1-Pad3)") (class "Default")
      (node (ref "SW13") (pin "3") (pinfunction "P1_3") (pintype "passive"))
    )
    (net (code "141") (name "unconnected-(SW13-S1-Pad4)") (class "Default")
      (node (ref "SW13") (pin "4") (pinfunction "S1_4") (pintype "passive"))
    )
    (net (code "142") (name "unconnected-(SW14-P1-Pad3)") (class "Default")
      (node (ref "SW14") (pin "3") (pinfunction "P1_3") (pintype "passive"))
    )
    (net (code "143") (name "unconnected-(SW14-S1-Pad4)") (class "Default")
      (node (ref "SW14") (pin "4") (pinfunction "S1_4") (pintype "passive"))
    )
    (net (code "144") (name "unconnected-(SW15-P1-Pad3)") (class "Default")
      (node (ref "SW15") (pin "3") (pinfunction "P1_3") (pintype "passive"))
    )
    (net (code "145") (name "unconnected-(SW15-S1-Pad4)") (class "Default")
      (node (ref "SW15") (pin "4") (pinfunction "S1_4") (pintype "passive"))
    )
    (net (code "146") (name "unconnected-(SW16-P1-Pad3)") (class "Default")
      (node (ref "SW16") (pin "3") (pinfunction "P1_3") (pintype "passive"))
    )
    (net (code "147") (name "unconnected-(SW16-S1-Pad4)") (class "Default")
      (node (ref "SW16") (pin "4") (pinfunction "S1_4") (pintype "passive"))
    )
  )
)
